# CONNECTOR.net
KiCad netlist of a schematic drawn in Altium Designer
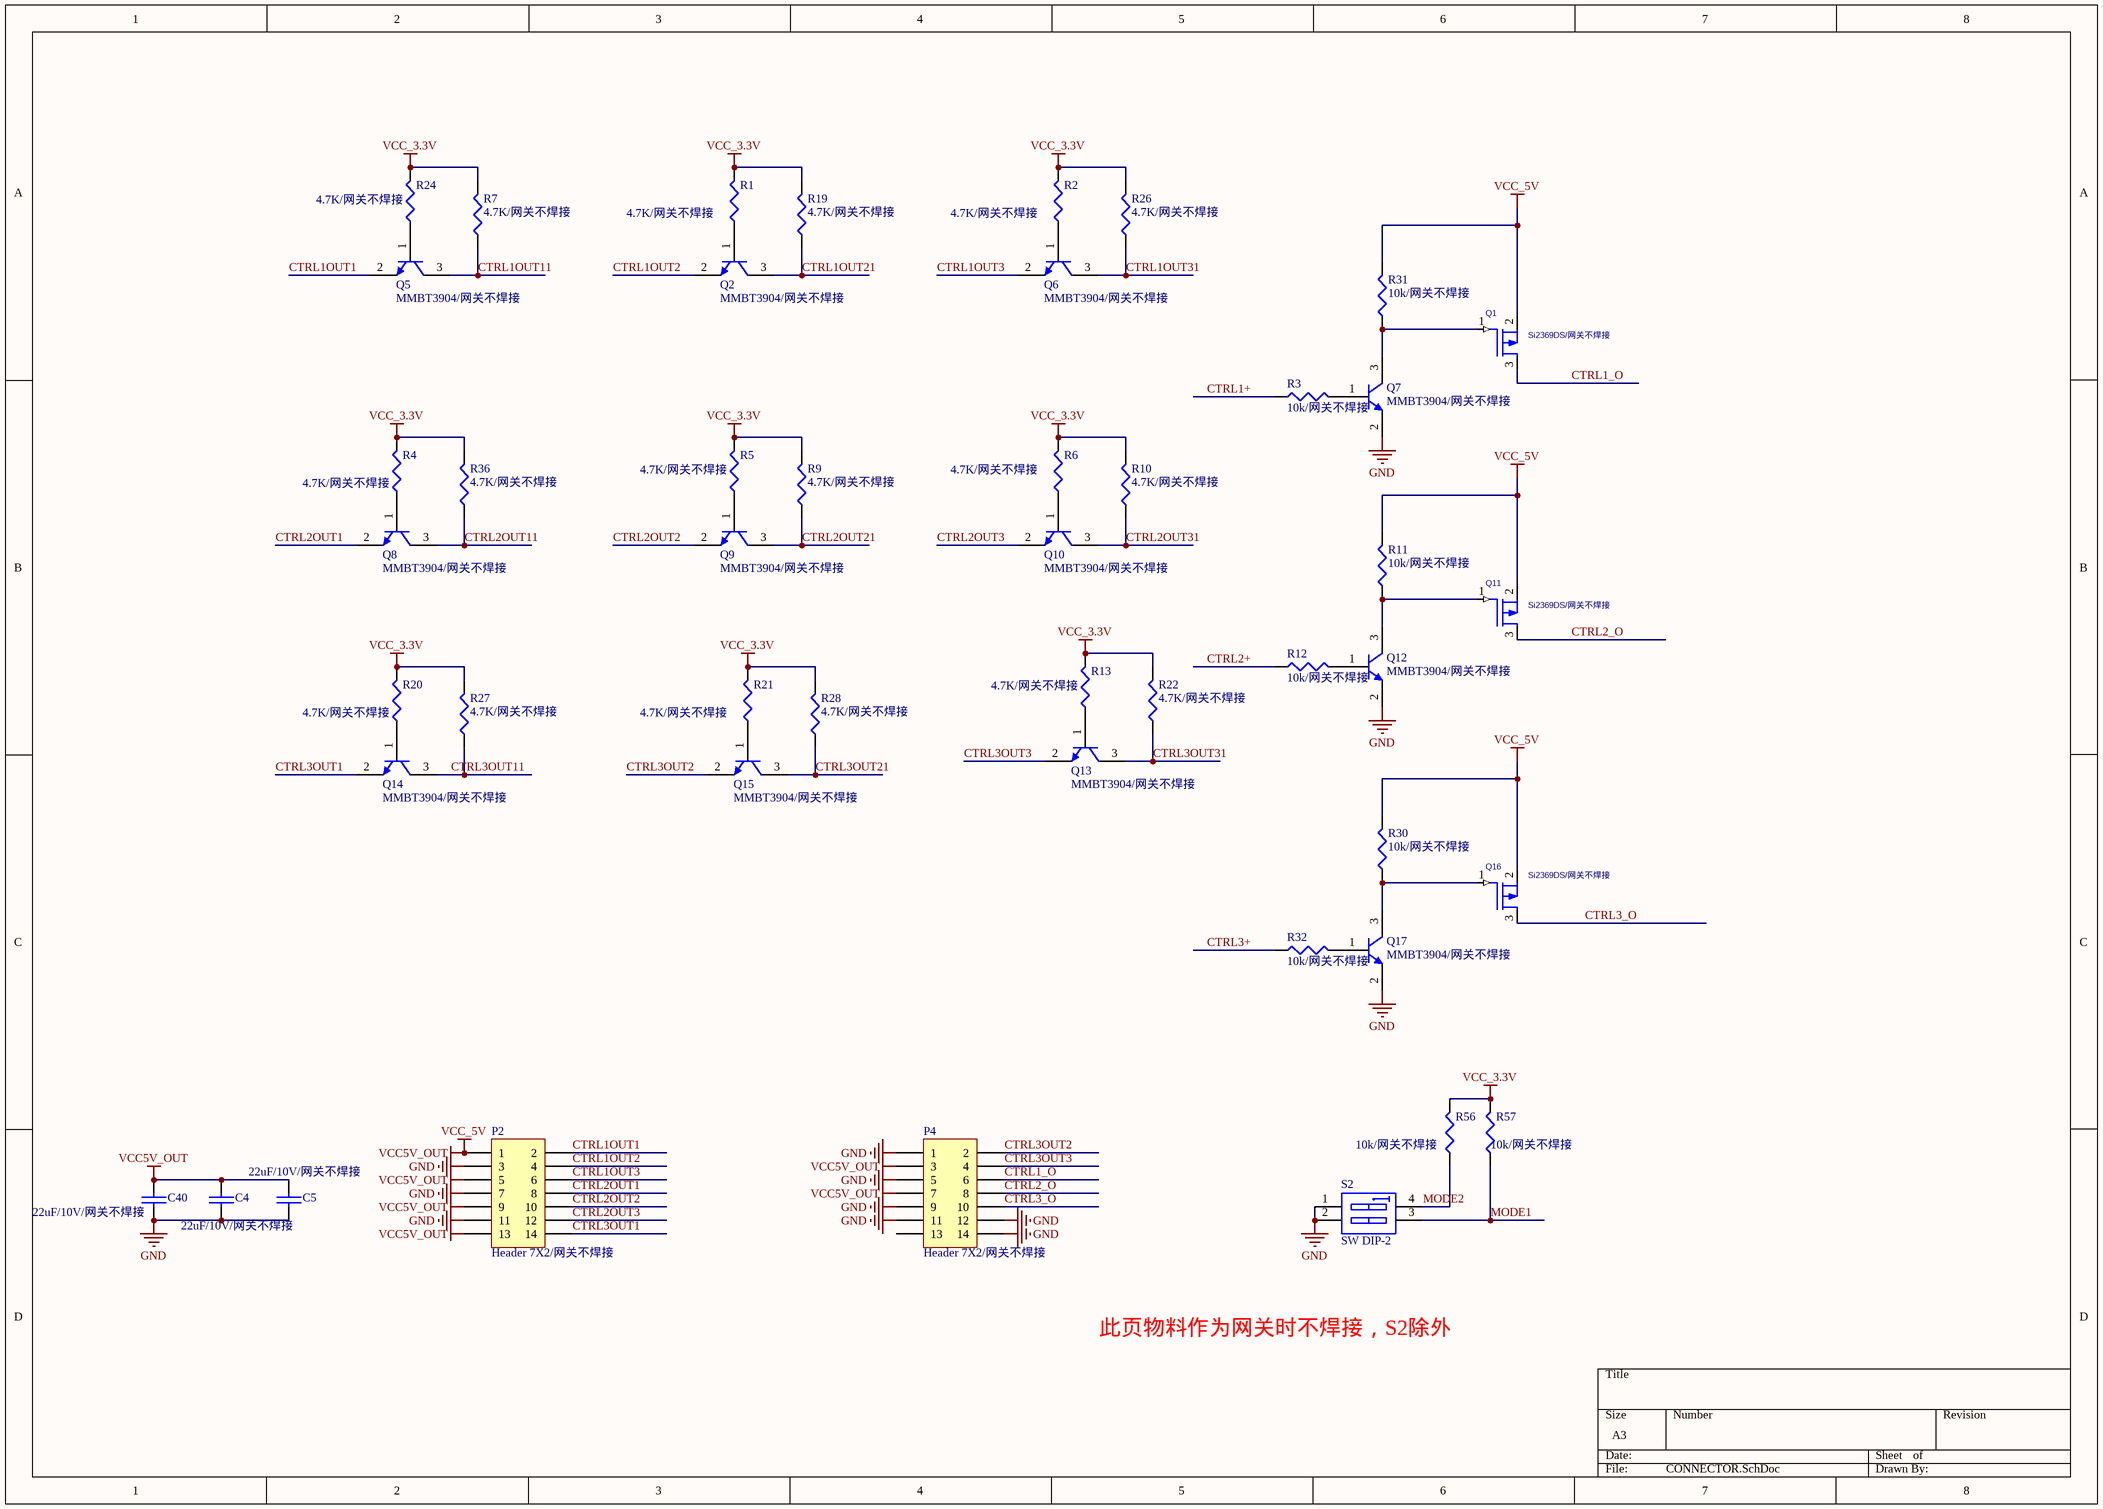
[diagram p0: CONNECTOR.SchDoc]

(export (version "E")
  (design (tool "Eeschema 10.0.6"))
  (components
    (comp (ref "C4")
      (value "22uF/10V/网关不焊接")
      (footprint "1206C")
      (description "Capacitor")
      (libsource (lib "ZWLIntegrated_Library") (part "CAP"))
    )
    (comp (ref "C5")
      (value "22uF/10V/网关不焊接")
      (footprint "1206C")
      (description "Capacitor")
      (libsource (lib "ZWLIntegrated_Library") (part "CAP"))
    )
    (comp (ref "C40")
      (value "22uF/10V/网关不焊接")
      (footprint "1206C")
      (description "Capacitor")
      (libsource (lib "ZWLIntegrated_Library") (part "CAP"))
    )
    (comp (ref "P2")
      (value "Header 7X2/网关不焊接")
      (footprint "14X2.54MMZ")
      (description "Header, 7-Pin, Dual row")
      (fields (field (name "PUBLISHER") "Altium Limited"))
      (libsource (lib "Miscellaneous Connectors") (part "Header 7X2"))
    )
    (comp (ref "P4")
      (value "Header 7X2/网关不焊接")
      (footprint "14X2.54MMZ")
      (description "Header, 7-Pin, Dual row")
      (fields (field (name "PUBLISHER") "Altium Limited"))
      (libsource (lib "Miscellaneous Connectors") (part "Header 7X2"))
    )
    (comp (ref "Q1") (value "Si2369DS/网关不焊接") (footprint "SOT23") (libsource (lib "*") (part "MOSFET P_1")))
    (comp (ref "Q2") (value "MMBT3904/网关不焊接") (footprint "SOT23-3") (libsource (lib "Schlib1") (part "NPN")))
    (comp (ref "Q5") (value "MMBT3904/网关不焊接") (footprint "SOT23-3") (libsource (lib "Schlib1") (part "NPN")))
    (comp (ref "Q6") (value "MMBT3904/网关不焊接") (footprint "SOT23-3") (libsource (lib "Schlib1") (part "NPN")))
    (comp (ref "Q7") (value "MMBT3904/网关不焊接") (footprint "SOT23-3") (libsource (lib "Schlib1") (part "NPN")))
    (comp (ref "Q8") (value "MMBT3904/网关不焊接") (footprint "SOT23-3") (libsource (lib "Schlib1") (part "NPN")))
    (comp (ref "Q9") (value "MMBT3904/网关不焊接") (footprint "SOT23-3") (libsource (lib "Schlib1") (part "NPN")))
    (comp (ref "Q10") (value "MMBT3904/网关不焊接") (footprint "SOT23-3") (libsource (lib "Schlib1") (part "NPN")))
    (comp (ref "Q11") (value "Si2369DS/网关不焊接") (footprint "SOT23") (libsource (lib "*") (part "MOSFET P_1")))
    (comp (ref "Q12") (value "MMBT3904/网关不焊接") (footprint "SOT23-3") (libsource (lib "Schlib1") (part "NPN")))
    (comp (ref "Q13") (value "MMBT3904/网关不焊接") (footprint "SOT23-3") (libsource (lib "Schlib1") (part "NPN")))
    (comp (ref "Q14") (value "MMBT3904/网关不焊接") (footprint "SOT23-3") (libsource (lib "Schlib1") (part "NPN")))
    (comp (ref "Q15") (value "MMBT3904/网关不焊接") (footprint "SOT23-3") (libsource (lib "Schlib1") (part "NPN")))
    (comp (ref "Q16") (value "Si2369DS/网关不焊接") (footprint "SOT23") (libsource (lib "*") (part "MOSFET P_1")))
    (comp (ref "Q17") (value "MMBT3904/网关不焊接") (footprint "SOT23-3") (libsource (lib "Schlib1") (part "NPN")))
    (comp (ref "R1")
      (value "4.7K/网关不焊接")
      (footprint "0603R")
      (libsource (lib "ZWLIntegrated_Library") (part "RES1"))
    )
    (comp (ref "R2")
      (value "4.7K/网关不焊接")
      (footprint "0603R")
      (libsource (lib "ZWLIntegrated_Library") (part "RES1"))
    )
    (comp (ref "R3")
      (value "10k/网关不焊接")
      (footprint "0603R")
      (libsource (lib "ZWLIntegrated_Library") (part "RES1"))
    )
    (comp (ref "R4")
      (value "4.7K/网关不焊接")
      (footprint "0603R")
      (libsource (lib "ZWLIntegrated_Library") (part "RES1"))
    )
    (comp (ref "R5")
      (value "4.7K/网关不焊接")
      (footprint "0603R")
      (libsource (lib "ZWLIntegrated_Library") (part "RES1"))
    )
    (comp (ref "R6")
      (value "4.7K/网关不焊接")
      (footprint "0603R")
      (libsource (lib "ZWLIntegrated_Library") (part "RES1"))
    )
    (comp (ref "R7")
      (value "4.7K/网关不焊接")
      (footprint "0603R")
      (libsource (lib "ZWLIntegrated_Library") (part "RES1"))
    )
    (comp (ref "R9")
      (value "4.7K/网关不焊接")
      (footprint "0603R")
      (libsource (lib "ZWLIntegrated_Library") (part "RES1"))
    )
    (comp (ref "R10")
      (value "4.7K/网关不焊接")
      (footprint "0603R")
      (libsource (lib "ZWLIntegrated_Library") (part "RES1"))
    )
    (comp (ref "R11")
      (value "10k/网关不焊接")
      (footprint "0603R")
      (libsource (lib "ZWLIntegrated_Library") (part "RES1"))
    )
    (comp (ref "R12")
      (value "10k/网关不焊接")
      (footprint "0603R")
      (libsource (lib "ZWLIntegrated_Library") (part "RES1"))
    )
    (comp (ref "R13")
      (value "4.7K/网关不焊接")
      (footprint "0603R")
      (libsource (lib "ZWLIntegrated_Library") (part "RES1"))
    )
    (comp (ref "R19")
      (value "4.7K/网关不焊接")
      (footprint "0603R")
      (libsource (lib "ZWLIntegrated_Library") (part "RES1"))
    )
    (comp (ref "R20")
      (value "4.7K/网关不焊接")
      (footprint "0603R")
      (libsource (lib "ZWLIntegrated_Library") (part "RES1"))
    )
    (comp (ref "R21")
      (value "4.7K/网关不焊接")
      (footprint "0603R")
      (libsource (lib "ZWLIntegrated_Library") (part "RES1"))
    )
    (comp (ref "R22")
      (value "4.7K/网关不焊接")
      (footprint "0603R")
      (libsource (lib "ZWLIntegrated_Library") (part "RES1"))
    )
    (comp (ref "R24")
      (value "4.7K/网关不焊接")
      (footprint "0603R")
      (libsource (lib "ZWLIntegrated_Library") (part "RES1"))
    )
    (comp (ref "R26")
      (value "4.7K/网关不焊接")
      (footprint "0603R")
      (libsource (lib "ZWLIntegrated_Library") (part "RES1"))
    )
    (comp (ref "R27")
      (value "4.7K/网关不焊接")
      (footprint "0603R")
      (libsource (lib "ZWLIntegrated_Library") (part "RES1"))
    )
    (comp (ref "R28")
      (value "4.7K/网关不焊接")
      (footprint "0603R")
      (libsource (lib "ZWLIntegrated_Library") (part "RES1"))
    )
    (comp (ref "R30")
      (value "10k/网关不焊接")
      (footprint "0603R")
      (libsource (lib "ZWLIntegrated_Library") (part "RES1"))
    )
    (comp (ref "R31")
      (value "10k/网关不焊接")
      (footprint "0603R")
      (libsource (lib "ZWLIntegrated_Library") (part "RES1"))
    )
    (comp (ref "R32")
      (value "10k/网关不焊接")
      (footprint "0603R")
      (libsource (lib "ZWLIntegrated_Library") (part "RES1"))
    )
    (comp (ref "R36")
      (value "4.7K/网关不焊接")
      (footprint "0603R")
      (libsource (lib "ZWLIntegrated_Library") (part "RES1"))
    )
    (comp (ref "R56")
      (value "10k/网关不焊接")
      (footprint "0603R")
      (libsource (lib "ZWLIntegrated_Library") (part "RES1"))
    )
    (comp (ref "R57")
      (value "10k/网关不焊接")
      (footprint "0603R")
      (libsource (lib "ZWLIntegrated_Library") (part "RES1"))
    )
    (comp (ref "S2")
      (value "SW DIP-2")
      (footprint "SW_SMT_4")
      (description "DIP Switch, 2 Position, SPST")
      (fields (field (name "PUBLISHER") "Altium Limited"))
      (libsource (lib "Miscellaneous Devices") (part "SW DIP-2"))
    )
  )
  (nets
    (net (code "1") (name "/CTRL1+") (class "Default")
      (node (ref "R3") (pin "1") (pinfunction "1_1") (pintype "passive"))
    )
    (net (code "2") (name "/CTRL1OUT1") (class "Default")
      (node (ref "P2") (pin "2") (pinfunction "2_2") (pintype "passive"))
      (node (ref "Q5") (pin "2") (pinfunction "E_2") (pintype "passive"))
    )
    (net (code "3") (name "/CTRL1OUT2") (class "Default")
      (node (ref "P2") (pin "4") (pinfunction "4_4") (pintype "passive"))
      (node (ref "Q2") (pin "2") (pinfunction "E_2") (pintype "passive"))
    )
    (net (code "4") (name "/CTRL1OUT3") (class "Default")
      (node (ref "P2") (pin "6") (pinfunction "6_6") (pintype "passive"))
      (node (ref "Q6") (pin "2") (pinfunction "E_2") (pintype "passive"))
    )
    (net (code "5") (name "/CTRL1OUT11") (class "Default")
      (node (ref "Q5") (pin "3") (pinfunction "C_3") (pintype "passive"))
      (node (ref "R7") (pin "1") (pinfunction "1_1") (pintype "passive"))
    )
    (net (code "6") (name "/CTRL1OUT21") (class "Default")
      (node (ref "Q2") (pin "3") (pinfunction "C_3") (pintype "passive"))
      (node (ref "R19") (pin "1") (pinfunction "1_1") (pintype "passive"))
    )
    (net (code "7") (name "/CTRL1OUT31") (class "Default")
      (node (ref "Q6") (pin "3") (pinfunction "C_3") (pintype "passive"))
      (node (ref "R26") (pin "1") (pinfunction "1_1") (pintype "passive"))
    )
    (net (code "8") (name "/CTRL1_O") (class "Default")
      (node (ref "P4") (pin "6") (pinfunction "6_6") (pintype "passive"))
      (node (ref "Q1") (pin "3") (pinfunction "SOURCE_3") (pintype "passive"))
    )
    (net (code "9") (name "/CTRL2+") (class "Default")
      (node (ref "R12") (pin "1") (pinfunction "1_1") (pintype "passive"))
    )
    (net (code "10") (name "/CTRL2OUT1") (class "Default")
      (node (ref "P2") (pin "8") (pinfunction "8_8") (pintype "passive"))
      (node (ref "Q8") (pin "2") (pinfunction "E_2") (pintype "passive"))
    )
    (net (code "11") (name "/CTRL2OUT2") (class "Default")
      (node (ref "P2") (pin "10") (pinfunction "10_10") (pintype "passive"))
      (node (ref "Q9") (pin "2") (pinfunction "E_2") (pintype "passive"))
    )
    (net (code "12") (name "/CTRL2OUT3") (class "Default")
      (node (ref "P2") (pin "12") (pinfunction "12_12") (pintype "passive"))
      (node (ref "Q10") (pin "2") (pinfunction "E_2") (pintype "passive"))
    )
    (net (code "13") (name "/CTRL2OUT11") (class "Default")
      (node (ref "Q8") (pin "3") (pinfunction "C_3") (pintype "passive"))
      (node (ref "R36") (pin "1") (pinfunction "1_1") (pintype "passive"))
    )
    (net (code "14") (name "/CTRL2OUT21") (class "Default")
      (node (ref "Q9") (pin "3") (pinfunction "C_3") (pintype "passive"))
      (node (ref "R9") (pin "1") (pinfunction "1_1") (pintype "passive"))
    )
    (net (code "15") (name "/CTRL2OUT31") (class "Default")
      (node (ref "Q10") (pin "3") (pinfunction "C_3") (pintype "passive"))
      (node (ref "R10") (pin "1") (pinfunction "1_1") (pintype "passive"))
    )
    (net (code "16") (name "/CTRL2_O") (class "Default")
      (node (ref "P4") (pin "8") (pinfunction "8_8") (pintype "passive"))
      (node (ref "Q11") (pin "3") (pinfunction "SOURCE_3") (pintype "passive"))
    )
    (net (code "17") (name "/CTRL3+") (class "Default")
      (node (ref "R32") (pin "1") (pinfunction "1_1") (pintype "passive"))
    )
    (net (code "18") (name "/CTRL3OUT1") (class "Default")
      (node (ref "P2") (pin "14") (pinfunction "14_14") (pintype "passive"))
      (node (ref "Q14") (pin "2") (pinfunction "E_2") (pintype "passive"))
    )
    (net (code "19") (name "/CTRL3OUT2") (class "Default")
      (node (ref "P4") (pin "2") (pinfunction "2_2") (pintype "passive"))
      (node (ref "Q15") (pin "2") (pinfunction "E_2") (pintype "passive"))
    )
    (net (code "20") (name "/CTRL3OUT3") (class "Default")
      (node (ref "P4") (pin "4") (pinfunction "4_4") (pintype "passive"))
      (node (ref "Q13") (pin "2") (pinfunction "E_2") (pintype "passive"))
    )
    (net (code "21") (name "/CTRL3OUT11") (class "Default")
      (node (ref "Q14") (pin "3") (pinfunction "C_3") (pintype "passive"))
      (node (ref "R27") (pin "1") (pinfunction "1_1") (pintype "passive"))
    )
    (net (code "22") (name "/CTRL3OUT21") (class "Default")
      (node (ref "Q15") (pin "3") (pinfunction "C_3") (pintype "passive"))
      (node (ref "R28") (pin "1") (pinfunction "1_1") (pintype "passive"))
    )
    (net (code "23") (name "/CTRL3OUT31") (class "Default")
      (node (ref "Q13") (pin "3") (pinfunction "C_3") (pintype "passive"))
      (node (ref "R22") (pin "1") (pinfunction "1_1") (pintype "passive"))
    )
    (net (code "24") (name "/CTRL3_O") (class "Default")
      (node (ref "P4") (pin "10") (pinfunction "10_10") (pintype "passive"))
      (node (ref "Q16") (pin "3") (pinfunction "SOURCE_3") (pintype "passive"))
    )
    (net (code "25") (name "/MODE1") (class "Default")
      (node (ref "R57") (pin "1") (pinfunction "1_1") (pintype "passive"))
      (node (ref "S2") (pin "3") (pinfunction "B2_3") (pintype "passive"))
    )
    (net (code "26") (name "/MODE2") (class "Default")
      (node (ref "R56") (pin "1") (pinfunction "1_1") (pintype "passive"))
      (node (ref "S2") (pin "4") (pinfunction "B1_4") (pintype "passive"))
    )
    (net (code "27") (name "GND") (class "Default")
      (node (ref "C4") (pin "2") (pinfunction "2_2") (pintype "passive"))
      (node (ref "C40") (pin "2") (pinfunction "2_2") (pintype "passive"))
      (node (ref "C5") (pin "2") (pinfunction "2_2") (pintype "passive"))
      (node (ref "P2") (pin "11") (pinfunction "11_11") (pintype "passive"))
      (node (ref "P2") (pin "3") (pinfunction "3_3") (pintype "passive"))
      (node (ref "P2") (pin "7") (pinfunction "7_7") (pintype "passive"))
      (node (ref "P4") (pin "1") (pinfunction "1_1") (pintype "passive"))
      (node (ref "P4") (pin "11") (pinfunction "11_11") (pintype "passive"))
      (node (ref "P4") (pin "12") (pinfunction "12_12") (pintype "passive"))
      (node (ref "P4") (pin "14") (pinfunction "14_14") (pintype "passive"))
      (node (ref "P4") (pin "5") (pinfunction "5_5") (pintype "passive"))
      (node (ref "P4") (pin "9") (pinfunction "9_9") (pintype "passive"))
      (node (ref "Q12") (pin "2") (pinfunction "E_2") (pintype "passive"))
      (node (ref "Q17") (pin "2") (pinfunction "E_2") (pintype "passive"))
      (node (ref "Q7") (pin "2") (pinfunction "E_2") (pintype "passive"))
      (node (ref "S2") (pin "1") (pinfunction "A1_1") (pintype "passive"))
      (node (ref "S2") (pin "2") (pinfunction "A2_2") (pintype "passive"))
    )
    (net (code "28") (name "Net-(Q1-GATE)") (class "Default")
      (node (ref "Q1") (pin "1") (pinfunction "GATE_1") (pintype "input"))
      (node (ref "Q7") (pin "3") (pinfunction "C_3") (pintype "passive"))
      (node (ref "R31") (pin "1") (pinfunction "1_1") (pintype "passive"))
    )
    (net (code "29") (name "Net-(Q2-B)") (class "Default")
      (node (ref "Q2") (pin "1") (pinfunction "B_1") (pintype "passive"))
      (node (ref "R1") (pin "1") (pinfunction "1_1") (pintype "passive"))
    )
    (net (code "30") (name "Net-(Q5-B)") (class "Default")
      (node (ref "Q5") (pin "1") (pinfunction "B_1") (pintype "passive"))
      (node (ref "R24") (pin "1") (pinfunction "1_1") (pintype "passive"))
    )
    (net (code "31") (name "Net-(Q6-B)") (class "Default")
      (node (ref "Q6") (pin "1") (pinfunction "B_1") (pintype "passive"))
      (node (ref "R2") (pin "1") (pinfunction "1_1") (pintype "passive"))
    )
    (net (code "32") (name "Net-(Q7-B)") (class "Default")
      (node (ref "Q7") (pin "1") (pinfunction "B_1") (pintype "passive"))
      (node (ref "R3") (pin "2") (pinfunction "2_2") (pintype "passive"))
    )
    (net (code "33") (name "Net-(Q8-B)") (class "Default")
      (node (ref "Q8") (pin "1") (pinfunction "B_1") (pintype "passive"))
      (node (ref "R4") (pin "1") (pinfunction "1_1") (pintype "passive"))
    )
    (net (code "34") (name "Net-(Q9-B)") (class "Default")
      (node (ref "Q9") (pin "1") (pinfunction "B_1") (pintype "passive"))
      (node (ref "R5") (pin "1") (pinfunction "1_1") (pintype "passive"))
    )
    (net (code "35") (name "Net-(Q10-B)") (class "Default")
      (node (ref "Q10") (pin "1") (pinfunction "B_1") (pintype "passive"))
      (node (ref "R6") (pin "1") (pinfunction "1_1") (pintype "passive"))
    )
    (net (code "36") (name "Net-(Q11-GATE)") (class "Default")
      (node (ref "Q11") (pin "1") (pinfunction "GATE_1") (pintype "input"))
      (node (ref "Q12") (pin "3") (pinfunction "C_3") (pintype "passive"))
      (node (ref "R11") (pin "1") (pinfunction "1_1") (pintype "passive"))
    )
    (net (code "37") (name "Net-(Q12-B)") (class "Default")
      (node (ref "Q12") (pin "1") (pinfunction "B_1") (pintype "passive"))
      (node (ref "R12") (pin "2") (pinfunction "2_2") (pintype "passive"))
    )
    (net (code "38") (name "Net-(Q13-B)") (class "Default")
      (node (ref "Q13") (pin "1") (pinfunction "B_1") (pintype "passive"))
      (node (ref "R13") (pin "1") (pinfunction "1_1") (pintype "passive"))
    )
    (net (code "39") (name "Net-(Q14-B)") (class "Default")
      (node (ref "Q14") (pin "1") (pinfunction "B_1") (pintype "passive"))
      (node (ref "R20") (pin "1") (pinfunction "1_1") (pintype "passive"))
    )
    (net (code "40") (name "Net-(Q15-B)") (class "Default")
      (node (ref "Q15") (pin "1") (pinfunction "B_1") (pintype "passive"))
      (node (ref "R21") (pin "1") (pinfunction "1_1") (pintype "passive"))
    )
    (net (code "41") (name "Net-(Q16-GATE)") (class "Default")
      (node (ref "Q16") (pin "1") (pinfunction "GATE_1") (pintype "input"))
      (node (ref "Q17") (pin "3") (pinfunction "C_3") (pintype "passive"))
      (node (ref "R30") (pin "1") (pinfunction "1_1") (pintype "passive"))
    )
    (net (code "42") (name "Net-(Q17-B)") (class "Default")
      (node (ref "Q17") (pin "1") (pinfunction "B_1") (pintype "passive"))
      (node (ref "R32") (pin "2") (pinfunction "2_2") (pintype "passive"))
    )
    (net (code "43") (name "VCC5V_OUT") (class "Default")
      (node (ref "C4") (pin "1") (pinfunction "1_1") (pintype "passive"))
      (node (ref "C40") (pin "1") (pinfunction "1_1") (pintype "passive"))
      (node (ref "C5") (pin "1") (pinfunction "1_1") (pintype "passive"))
      (node (ref "P2") (pin "1") (pinfunction "1_1") (pintype "passive"))
      (node (ref "P2") (pin "13") (pinfunction "13_13") (pintype "passive"))
      (node (ref "P2") (pin "5") (pinfunction "5_5") (pintype "passive"))
      (node (ref "P2") (pin "9") (pinfunction "9_9") (pintype "passive"))
      (node (ref "P4") (pin "3") (pinfunction "3_3") (pintype "passive"))
      (node (ref "P4") (pin "7") (pinfunction "7_7") (pintype "passive"))
      (node (ref "Q1") (pin "2") (pinfunction "DRAIN_2") (pintype "passive"))
      (node (ref "Q11") (pin "2") (pinfunction "DRAIN_2") (pintype "passive"))
      (node (ref "Q16") (pin "2") (pinfunction "DRAIN_2") (pintype "passive"))
      (node (ref "R11") (pin "2") (pinfunction "2_2") (pintype "passive"))
      (node (ref "R30") (pin "2") (pinfunction "2_2") (pintype "passive"))
      (node (ref "R31") (pin "2") (pinfunction "2_2") (pintype "passive"))
    )
    (net (code "44") (name "VCC_3.3V") (class "Default")
      (node (ref "R1") (pin "2") (pinfunction "2_2") (pintype "passive"))
      (node (ref "R10") (pin "2") (pinfunction "2_2") (pintype "passive"))
      (node (ref "R13") (pin "2") (pinfunction "2_2") (pintype "passive"))
      (node (ref "R19") (pin "2") (pinfunction "2_2") (pintype "passive"))
      (node (ref "R2") (pin "2") (pinfunction "2_2") (pintype "passive"))
      (node (ref "R20") (pin "2") (pinfunction "2_2") (pintype "passive"))
      (node (ref "R21") (pin "2") (pinfunction "2_2") (pintype "passive"))
      (node (ref "R22") (pin "2") (pinfunction "2_2") (pintype "passive"))
      (node (ref "R24") (pin "2") (pinfunction "2_2") (pintype "passive"))
      (node (ref "R26") (pin "2") (pinfunction "2_2") (pintype "passive"))
      (node (ref "R27") (pin "2") (pinfunction "2_2") (pintype "passive"))
      (node (ref "R28") (pin "2") (pinfunction "2_2") (pintype "passive"))
      (node (ref "R36") (pin "2") (pinfunction "2_2") (pintype "passive"))
      (node (ref "R4") (pin "2") (pinfunction "2_2") (pintype "passive"))
      (node (ref "R5") (pin "2") (pinfunction "2_2") (pintype "passive"))
      (node (ref "R56") (pin "2") (pinfunction "2_2") (pintype "passive"))
      (node (ref "R57") (pin "2") (pinfunction "2_2") (pintype "passive"))
      (node (ref "R6") (pin "2") (pinfunction "2_2") (pintype "passive"))
      (node (ref "R7") (pin "2") (pinfunction "2_2") (pintype "passive"))
      (node (ref "R9") (pin "2") (pinfunction "2_2") (pintype "passive"))
    )
    (net (code "45") (name "unconnected-(P4-Pad13)") (class "Default")
      (node (ref "P4") (pin "13") (pinfunction "13_13") (pintype "passive"))
    )
  )
)
